# arduino_connections.net
KiCad netlist of a schematic drawn in Altium Designer
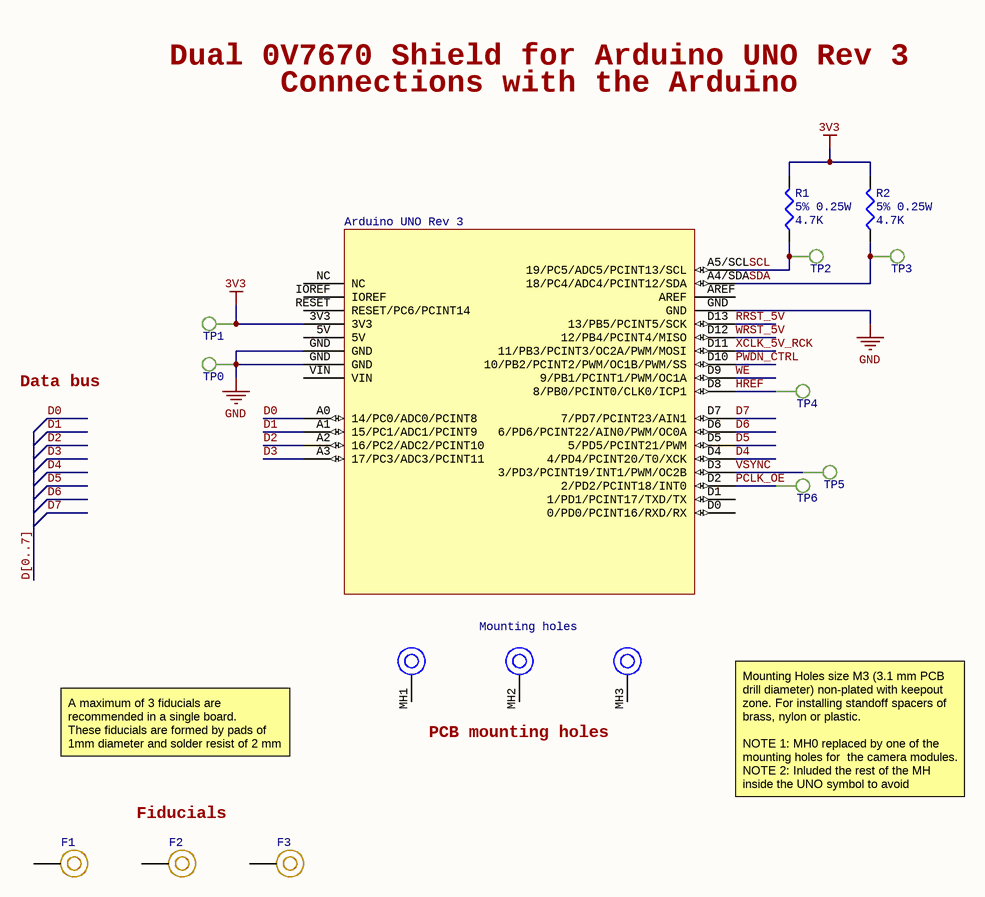
[diagram p0: arduino_connections.SchDoc]

(export (version "E")
  (design (tool "Eeschema 10.0.6"))
  (components
    (comp (ref "F1")
      (value "Fiducial_1mm_2mm")
      (footprint "FIDUCIAL_1MM_2MM")
      (description "Fiducial 1mm pad, 2mm solder resist")
      (libsource (lib "shield_SCH_LIB") (part "Fiducial_1mm_2mm"))
    )
    (comp (ref "F2")
      (value "Fiducial_1mm_2mm")
      (footprint "FIDUCIAL_1MM_2MM")
      (description "Fiducial 1mm pad, 2mm solder resist")
      (libsource (lib "shield_SCH_LIB") (part "Fiducial_1mm_2mm"))
    )
    (comp (ref "F3")
      (value "Fiducial_1mm_2mm")
      (footprint "FIDUCIAL_1MM_2MM")
      (description "Fiducial 1mm pad, 2mm solder resist")
      (libsource (lib "shield_SCH_LIB") (part "Fiducial_1mm_2mm"))
    )
    (comp (ref "MCU1")
      (value "Arduino UNO Rev 3")
      (footprint "Arduino UNO Rev 3")
      (description "Arduino UNO Rev 3 pinout")
      (libsource (lib "shield_SCH_LIB") (part "Arduino UNO Rev 3"))
    )
    (comp (ref "R1")
      (value "5% 0.25W")
      (footprint "0603 RES")
      (description "SMD Resistor 4.7 KOhm 5% 0.1W 0603")
      (fields (field (name "ALTIUM_VALUE") "4.7K") (field (name "PUBLISHER") "Altium Limited"))
      (libsource (lib "shield_SCH_LIB") (part "Res4K7"))
    )
    (comp (ref "R2")
      (value "5% 0.25W")
      (footprint "0603 RES")
      (description "SMD Resistor 4.7 KOhm 5% 0.1W 0603")
      (fields (field (name "ALTIUM_VALUE") "4.7K") (field (name "PUBLISHER") "Altium Limited"))
      (libsource (lib "shield_SCH_LIB") (part "Res4K7"))
    )
    (comp (ref "TP0")
      (value "Test Point Pad")
      (footprint "TEST POINT PAD")
      (description "Test point - PCB Pad type.")
      (libsource (lib "shield_SCH_LIB") (part "Test Point Pad"))
    )
    (comp (ref "TP1")
      (value "Test Point Pad")
      (footprint "TEST POINT PAD")
      (description "Test point - PCB Pad type.")
      (libsource (lib "shield_SCH_LIB") (part "Test Point Pad"))
    )
    (comp (ref "TP2")
      (value "Test Point Pad")
      (footprint "TEST POINT PAD")
      (description "Test point - PCB Pad type.")
      (libsource (lib "shield_SCH_LIB") (part "Test Point Pad"))
    )
    (comp (ref "TP3")
      (value "Test Point Pad")
      (footprint "TEST POINT PAD")
      (description "Test point - PCB Pad type.")
      (libsource (lib "shield_SCH_LIB") (part "Test Point Pad"))
    )
    (comp (ref "TP4")
      (value "Test Point Pad")
      (footprint "TEST POINT PAD")
      (description "Test point - PCB Pad type.")
      (libsource (lib "shield_SCH_LIB") (part "Test Point Pad"))
    )
    (comp (ref "TP5")
      (value "Test Point Pad")
      (footprint "TEST POINT PAD")
      (description "Test point - PCB Pad type.")
      (libsource (lib "shield_SCH_LIB") (part "Test Point Pad"))
    )
    (comp (ref "TP6")
      (value "Test Point Pad")
      (footprint "TEST POINT PAD")
      (description "Test point - PCB Pad type.")
      (libsource (lib "shield_SCH_LIB") (part "Test Point Pad"))
    )
  )
  (nets
    (net (code "1") (name "/D0") (class "Default")
      (node (ref "MCU1") (pin "A0") (pinfunction "14/PC0/ADC0/PCINT8_A0") (pintype "bidirectional"))
    )
    (net (code "2") (name "/D1") (class "Default")
      (node (ref "MCU1") (pin "A1") (pinfunction "15/PC1/ADC1/PCINT9_A1") (pintype "bidirectional"))
    )
    (net (code "3") (name "/D2") (class "Default")
      (node (ref "MCU1") (pin "A2") (pinfunction "16/PC2/ADC2/PCINT10_A2") (pintype "bidirectional"))
    )
    (net (code "4") (name "/D3") (class "Default")
      (node (ref "MCU1") (pin "A3") (pinfunction "17/PC3/ADC3/PCINT11_A3") (pintype "bidirectional"))
    )
    (net (code "5") (name "/D4") (class "Default")
      (node (ref "MCU1") (pin "D4") (pinfunction "4/PD4/PCINT20/T0/XCK_D4") (pintype "bidirectional"))
    )
    (net (code "6") (name "/D5") (class "Default")
      (node (ref "MCU1") (pin "D5") (pinfunction "5/PD5/PCINT21/PWM_D5") (pintype "bidirectional"))
    )
    (net (code "7") (name "/D6") (class "Default")
      (node (ref "MCU1") (pin "D6") (pinfunction "6/PD6/PCINT22/AIN0/PWM/OC0A_D6") (pintype "bidirectional"))
    )
    (net (code "8") (name "/D7") (class "Default")
      (node (ref "MCU1") (pin "D7") (pinfunction "7/PD7/PCINT23/AIN1_D7") (pintype "bidirectional"))
    )
    (net (code "10") (name "/HREF") (class "Default")
      (node (ref "MCU1") (pin "D8") (pinfunction "8/PB0/PCINT0/CLK0/ICP1_D8") (pintype "bidirectional"))
      (node (ref "TP4") (pin "1") (pinfunction "1_1") (pintype "passive"))
    )
    (net (code "11") (name "/PCLK_OE") (class "Default")
      (node (ref "MCU1") (pin "D2") (pinfunction "2/PD2/PCINT18/INT0_D2") (pintype "bidirectional"))
      (node (ref "TP6") (pin "1") (pinfunction "1_1") (pintype "passive"))
    )
    (net (code "12") (name "/PWDN_CTRL") (class "Default")
      (node (ref "MCU1") (pin "D10") (pinfunction "10/PB2/PCINT2/PWM/OC1B/PWM/SS_D10") (pintype "bidirectional"))
    )
    (net (code "13") (name "/RRST_5V") (class "Default")
      (node (ref "MCU1") (pin "D13") (pinfunction "13/PB5/PCINT5/SCK_D13") (pintype "bidirectional"))
    )
    (net (code "14") (name "/SCL") (class "Default")
      (node (ref "MCU1") (pin "A5/SCL") (pinfunction "19/PC5/ADC5/PCINT13/SCL_A5/SCL") (pintype "bidirectional"))
      (node (ref "R1") (pin "1") (pinfunction "1_1") (pintype "passive"))
      (node (ref "TP2") (pin "1") (pinfunction "1_1") (pintype "passive"))
    )
    (net (code "15") (name "/SDA") (class "Default")
      (node (ref "MCU1") (pin "A4/SDA") (pinfunction "18/PC4/ADC4/PCINT12/SDA_A4/SDA") (pintype "bidirectional"))
      (node (ref "R2") (pin "1") (pinfunction "1_1") (pintype "passive"))
      (node (ref "TP3") (pin "1") (pinfunction "1_1") (pintype "passive"))
    )
    (net (code "16") (name "/VSYNC") (class "Default")
      (node (ref "MCU1") (pin "D3") (pinfunction "3/PD3/PCINT19/INT1/PWM/OC2B_D3") (pintype "bidirectional"))
      (node (ref "TP5") (pin "1") (pinfunction "1_1") (pintype "passive"))
    )
    (net (code "17") (name "/WE") (class "Default")
      (node (ref "MCU1") (pin "D9") (pinfunction "9/PB1/PCINT1/PWM/OC1A_D9") (pintype "bidirectional"))
    )
    (net (code "18") (name "/WRST_5V") (class "Default")
      (node (ref "MCU1") (pin "D12") (pinfunction "12/PB4/PCINT4/MISO_D12") (pintype "bidirectional"))
    )
    (net (code "19") (name "/XCLK_5V_RCK") (class "Default")
      (node (ref "MCU1") (pin "D11") (pinfunction "11/PB3/PCINT3/OC2A/PWM/MOSI_D11") (pintype "bidirectional"))
    )
    (net (code "20") (name "3V3") (class "Default")
      (node (ref "MCU1") (pin "3V3") (pinfunction "3V3_3V3") (pintype "power_in"))
      (node (ref "R1") (pin "2") (pinfunction "2_2") (pintype "passive"))
      (node (ref "R2") (pin "2") (pinfunction "2_2") (pintype "passive"))
      (node (ref "TP1") (pin "1") (pinfunction "1_1") (pintype "passive"))
    )
    (net (code "21") (name "GND") (class "Default")
      (node (ref "MCU1") (pin "GND") (pinfunction "GND_GND") (pintype "power_in"))
      (node (ref "TP0") (pin "1") (pinfunction "1_1") (pintype "passive"))
    )
    (net (code "22") (name "unconnected-(F1-Pad1)") (class "Default")
      (node (ref "F1") (pin "1") (pinfunction "1_1") (pintype "passive"))
    )
    (net (code "23") (name "unconnected-(F2-Pad1)") (class "Default")
      (node (ref "F2") (pin "1") (pinfunction "1_1") (pintype "passive"))
    )
    (net (code "24") (name "unconnected-(F3-Pad1)") (class "Default")
      (node (ref "F3") (pin "1") (pinfunction "1_1") (pintype "passive"))
    )
    (net (code "25") (name "unconnected-(MCU1-0{slash}PD0{slash}PCINT16{slash}RXD{slash}RX-PadD0)") (class "Default")
      (node (ref "MCU1") (pin "D0") (pinfunction "0/PD0/PCINT16/RXD/RX_D0") (pintype "bidirectional"))
    )
    (net (code "26") (name "unconnected-(MCU1-1{slash}PD1{slash}PCINT17{slash}TXD{slash}TX-PadD1)") (class "Default")
      (node (ref "MCU1") (pin "D1") (pinfunction "1/PD1/PCINT17/TXD/TX_D1") (pintype "bidirectional"))
    )
    (net (code "27") (name "unconnected-(MCU1-Pad5V)") (class "Default")
      (node (ref "MCU1") (pin "5V") (pinfunction "5V_5V") (pintype "power_in"))
    )
    (net (code "28") (name "unconnected-(MCU1-PadAREF)") (class "Default")
      (node (ref "MCU1") (pin "AREF") (pinfunction "AREF_AREF") (pintype "passive"))
    )
    (net (code "29") (name "unconnected-(MCU1-PadIOREF)") (class "Default")
      (node (ref "MCU1") (pin "IOREF") (pinfunction "IOREF_IOREF") (pintype "passive"))
    )
    (net (code "30") (name "unconnected-(MCU1-PadMH1)") (class "Default")
      (node (ref "MCU1") (pin "MH1") (pinfunction "MH1_MH1") (pintype "passive"))
    )
    (net (code "31") (name "unconnected-(MCU1-PadMH2)") (class "Default")
      (node (ref "MCU1") (pin "MH2") (pinfunction "MH2_MH2") (pintype "passive"))
    )
    (net (code "32") (name "unconnected-(MCU1-PadMH3)") (class "Default")
      (node (ref "MCU1") (pin "MH3") (pinfunction "MH3_MH3") (pintype "passive"))
    )
    (net (code "33") (name "unconnected-(MCU1-PadNC)") (class "Default")
      (node (ref "MCU1") (pin "NC") (pinfunction "NC_NC") (pintype "passive"))
    )
    (net (code "34") (name "unconnected-(MCU1-PadVIN)") (class "Default")
      (node (ref "MCU1") (pin "VIN") (pinfunction "VIN_VIN") (pintype "power_in"))
    )
    (net (code "35") (name "unconnected-(MCU1-RESET{slash}PC6{slash}PCINT14-PadRESET)") (class "Default")
      (node (ref "MCU1") (pin "RESET") (pinfunction "RESET/PC6/PCINT14_RESET") (pintype "passive"))
    )
  )
)
